# DoubleThumbs.net
KiCad netlist of a schematic drawn in EAGLE
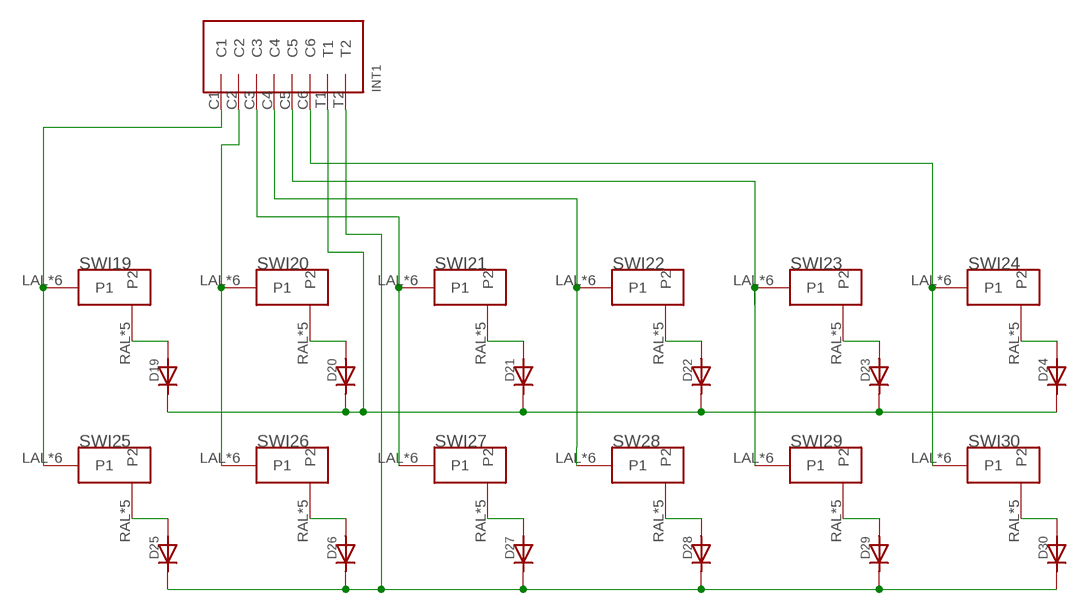
[diagram p0: schematic, sheet 1]

(export (version "E")
  (design (tool "Eeschema 10.0.6"))
  (components
    (comp (ref "D19")
      (value "DIODE")
      (footprint "eagle-import:DIODE_COMBO")
      (libsource (lib "eagle-import") (part "DIODE"))
    )
    (comp (ref "D20")
      (value "DIODE")
      (footprint "eagle-import:DIODE_COMBO")
      (libsource (lib "eagle-import") (part "DIODE"))
    )
    (comp (ref "D21")
      (value "DIODE")
      (footprint "eagle-import:DIODE_COMBO")
      (libsource (lib "eagle-import") (part "DIODE"))
    )
    (comp (ref "D22")
      (value "DIODE")
      (footprint "eagle-import:DIODE_COMBO")
      (libsource (lib "eagle-import") (part "DIODE"))
    )
    (comp (ref "D23")
      (value "DIODE")
      (footprint "eagle-import:DIODE_COMBO")
      (libsource (lib "eagle-import") (part "DIODE"))
    )
    (comp (ref "D24")
      (value "DIODE")
      (footprint "eagle-import:DIODE_COMBO")
      (libsource (lib "eagle-import") (part "DIODE"))
    )
    (comp (ref "D25")
      (value "DIODE")
      (footprint "eagle-import:DIODE_COMBO")
      (libsource (lib "eagle-import") (part "DIODE"))
    )
    (comp (ref "D26")
      (value "DIODE")
      (footprint "eagle-import:DIODE_COMBO")
      (libsource (lib "eagle-import") (part "DIODE"))
    )
    (comp (ref "D27")
      (value "DIODE")
      (footprint "eagle-import:DIODE_COMBO")
      (libsource (lib "eagle-import") (part "DIODE"))
    )
    (comp (ref "D28")
      (value "DIODE")
      (footprint "eagle-import:DIODE_COMBO")
      (libsource (lib "eagle-import") (part "DIODE"))
    )
    (comp (ref "D29")
      (value "DIODE")
      (footprint "eagle-import:DIODE_COMBO")
      (libsource (lib "eagle-import") (part "DIODE"))
    )
    (comp (ref "D30")
      (value "DIODE")
      (footprint "eagle-import:DIODE_COMBO")
      (libsource (lib "eagle-import") (part "DIODE"))
    )
    (comp (ref "INT1")
      (value "INTRCNNT4X2")
      (footprint "eagle-import:INTRRIBBON")
      (libsource (lib "eagle-import") (part "INTRCNNT4X2"))
    )
    (comp (ref "SW28")
      (value "MX/ALPSDOUBLESIDED")
      (footprint "eagle-import:DOUBLED_MX_ALPS")
      (libsource (lib "eagle-import") (part "MX/ALPSDOUBLESIDED"))
    )
    (comp (ref "SWI19")
      (value "MX/ALPSDOUBLESIDED")
      (footprint "eagle-import:DOUBLED_MX_ALPS")
      (libsource (lib "eagle-import") (part "MX/ALPSDOUBLESIDED"))
    )
    (comp (ref "SWI20")
      (value "MX/ALPSDOUBLESIDED")
      (footprint "eagle-import:DOUBLED_MX_ALPS")
      (libsource (lib "eagle-import") (part "MX/ALPSDOUBLESIDED"))
    )
    (comp (ref "SWI21")
      (value "MX/ALPSDOUBLESIDED")
      (footprint "eagle-import:DOUBLED_MX_ALPS")
      (libsource (lib "eagle-import") (part "MX/ALPSDOUBLESIDED"))
    )
    (comp (ref "SWI22")
      (value "MX/ALPSDOUBLESIDED")
      (footprint "eagle-import:DOUBLED_MX_ALPS")
      (libsource (lib "eagle-import") (part "MX/ALPSDOUBLESIDED"))
    )
    (comp (ref "SWI23")
      (value "MX/ALPSDOUBLESIDED")
      (footprint "eagle-import:DOUBLED_MX_ALPS")
      (libsource (lib "eagle-import") (part "MX/ALPSDOUBLESIDED"))
    )
    (comp (ref "SWI24")
      (value "MX/ALPSDOUBLESIDED")
      (footprint "eagle-import:DOUBLED_MX_ALPS")
      (libsource (lib "eagle-import") (part "MX/ALPSDOUBLESIDED"))
    )
    (comp (ref "SWI25")
      (value "MX/ALPSDOUBLESIDED")
      (footprint "eagle-import:DOUBLED_MX_ALPS")
      (libsource (lib "eagle-import") (part "MX/ALPSDOUBLESIDED"))
    )
    (comp (ref "SWI26")
      (value "MX/ALPSDOUBLESIDED")
      (footprint "eagle-import:DOUBLED_MX_ALPS")
      (libsource (lib "eagle-import") (part "MX/ALPSDOUBLESIDED"))
    )
    (comp (ref "SWI27")
      (value "MX/ALPSDOUBLESIDED")
      (footprint "eagle-import:DOUBLED_MX_ALPS")
      (libsource (lib "eagle-import") (part "MX/ALPSDOUBLESIDED"))
    )
    (comp (ref "SWI29")
      (value "MX/ALPSDOUBLESIDED")
      (footprint "eagle-import:DOUBLED_MX_ALPS")
      (libsource (lib "eagle-import") (part "MX/ALPSDOUBLESIDED"))
    )
    (comp (ref "SWI30")
      (value "MX/ALPSDOUBLESIDED")
      (footprint "eagle-import:DOUBLED_MX_ALPS")
      (libsource (lib "eagle-import") (part "MX/ALPSDOUBLESIDED"))
    )
  )
  (nets
    (net (code "1") (name "Net-(D19-AN-PadANOSB)") (class "Default")
      (node (ref "D19") (pin "ANOSB") (pinfunction "AN_ANOSB") (pintype "bidirectional"))
      (node (ref "D19") (pin "ANOST") (pinfunction "AN_ANOST") (pintype "bidirectional"))
      (node (ref "D19") (pin "ANOT") (pinfunction "AN_ANOT") (pintype "bidirectional"))
      (node (ref "SWI19") (pin "RAL") (pinfunction "P2_RAL") (pintype "bidirectional"))
      (node (ref "SWI19") (pin "RAR") (pinfunction "P2_RAR") (pintype "bidirectional"))
      (node (ref "SWI19") (pin "RCL") (pinfunction "P2_RCL") (pintype "bidirectional"))
      (node (ref "SWI19") (pin "RCR") (pinfunction "P2_RCR") (pintype "bidirectional"))
      (node (ref "SWI19") (pin "RLMID") (pinfunction "P2_RLMID") (pintype "bidirectional"))
    )
    (net (code "2") (name "Net-(D19-CAT-PadCATSB)") (class "Default")
      (node (ref "D19") (pin "CATSB") (pinfunction "CAT_CATSB") (pintype "bidirectional"))
      (node (ref "D19") (pin "CATST") (pinfunction "CAT_CATST") (pintype "bidirectional"))
      (node (ref "D19") (pin "CATT") (pinfunction "CAT_CATT") (pintype "bidirectional"))
      (node (ref "D20") (pin "CATSB") (pinfunction "CAT_CATSB") (pintype "bidirectional"))
      (node (ref "D20") (pin "CATST") (pinfunction "CAT_CATST") (pintype "bidirectional"))
      (node (ref "D20") (pin "CATT") (pinfunction "CAT_CATT") (pintype "bidirectional"))
      (node (ref "D21") (pin "CATSB") (pinfunction "CAT_CATSB") (pintype "bidirectional"))
      (node (ref "D21") (pin "CATST") (pinfunction "CAT_CATST") (pintype "bidirectional"))
      (node (ref "D21") (pin "CATT") (pinfunction "CAT_CATT") (pintype "bidirectional"))
      (node (ref "D22") (pin "CATSB") (pinfunction "CAT_CATSB") (pintype "bidirectional"))
      (node (ref "D22") (pin "CATST") (pinfunction "CAT_CATST") (pintype "bidirectional"))
      (node (ref "D22") (pin "CATT") (pinfunction "CAT_CATT") (pintype "bidirectional"))
      (node (ref "D23") (pin "CATSB") (pinfunction "CAT_CATSB") (pintype "bidirectional"))
      (node (ref "D23") (pin "CATST") (pinfunction "CAT_CATST") (pintype "bidirectional"))
      (node (ref "D23") (pin "CATT") (pinfunction "CAT_CATT") (pintype "bidirectional"))
      (node (ref "D24") (pin "CATSB") (pinfunction "CAT_CATSB") (pintype "bidirectional"))
      (node (ref "D24") (pin "CATST") (pinfunction "CAT_CATST") (pintype "bidirectional"))
      (node (ref "D24") (pin "CATT") (pinfunction "CAT_CATT") (pintype "bidirectional"))
      (node (ref "INT1") (pin "T1") (pinfunction "T1_T1") (pintype "bidirectional"))
    )
    (net (code "3") (name "Net-(D20-AN-PadANOSB)") (class "Default")
      (node (ref "D20") (pin "ANOSB") (pinfunction "AN_ANOSB") (pintype "bidirectional"))
      (node (ref "D20") (pin "ANOST") (pinfunction "AN_ANOST") (pintype "bidirectional"))
      (node (ref "D20") (pin "ANOT") (pinfunction "AN_ANOT") (pintype "bidirectional"))
      (node (ref "SWI20") (pin "RAL") (pinfunction "P2_RAL") (pintype "bidirectional"))
      (node (ref "SWI20") (pin "RAR") (pinfunction "P2_RAR") (pintype "bidirectional"))
      (node (ref "SWI20") (pin "RCL") (pinfunction "P2_RCL") (pintype "bidirectional"))
      (node (ref "SWI20") (pin "RCR") (pinfunction "P2_RCR") (pintype "bidirectional"))
      (node (ref "SWI20") (pin "RLMID") (pinfunction "P2_RLMID") (pintype "bidirectional"))
    )
    (net (code "4") (name "Net-(D21-AN-PadANOSB)") (class "Default")
      (node (ref "D21") (pin "ANOSB") (pinfunction "AN_ANOSB") (pintype "bidirectional"))
      (node (ref "D21") (pin "ANOST") (pinfunction "AN_ANOST") (pintype "bidirectional"))
      (node (ref "D21") (pin "ANOT") (pinfunction "AN_ANOT") (pintype "bidirectional"))
      (node (ref "SWI21") (pin "RAL") (pinfunction "P2_RAL") (pintype "bidirectional"))
      (node (ref "SWI21") (pin "RAR") (pinfunction "P2_RAR") (pintype "bidirectional"))
      (node (ref "SWI21") (pin "RCL") (pinfunction "P2_RCL") (pintype "bidirectional"))
      (node (ref "SWI21") (pin "RCR") (pinfunction "P2_RCR") (pintype "bidirectional"))
      (node (ref "SWI21") (pin "RLMID") (pinfunction "P2_RLMID") (pintype "bidirectional"))
    )
    (net (code "5") (name "Net-(D22-AN-PadANOSB)") (class "Default")
      (node (ref "D22") (pin "ANOSB") (pinfunction "AN_ANOSB") (pintype "bidirectional"))
      (node (ref "D22") (pin "ANOST") (pinfunction "AN_ANOST") (pintype "bidirectional"))
      (node (ref "D22") (pin "ANOT") (pinfunction "AN_ANOT") (pintype "bidirectional"))
      (node (ref "SWI22") (pin "RAL") (pinfunction "P2_RAL") (pintype "bidirectional"))
      (node (ref "SWI22") (pin "RAR") (pinfunction "P2_RAR") (pintype "bidirectional"))
      (node (ref "SWI22") (pin "RCL") (pinfunction "P2_RCL") (pintype "bidirectional"))
      (node (ref "SWI22") (pin "RCR") (pinfunction "P2_RCR") (pintype "bidirectional"))
      (node (ref "SWI22") (pin "RLMID") (pinfunction "P2_RLMID") (pintype "bidirectional"))
    )
    (net (code "6") (name "Net-(D23-AN-PadANOSB)") (class "Default")
      (node (ref "D23") (pin "ANOSB") (pinfunction "AN_ANOSB") (pintype "bidirectional"))
      (node (ref "D23") (pin "ANOST") (pinfunction "AN_ANOST") (pintype "bidirectional"))
      (node (ref "D23") (pin "ANOT") (pinfunction "AN_ANOT") (pintype "bidirectional"))
      (node (ref "SWI23") (pin "RAL") (pinfunction "P2_RAL") (pintype "bidirectional"))
      (node (ref "SWI23") (pin "RAR") (pinfunction "P2_RAR") (pintype "bidirectional"))
      (node (ref "SWI23") (pin "RCL") (pinfunction "P2_RCL") (pintype "bidirectional"))
      (node (ref "SWI23") (pin "RCR") (pinfunction "P2_RCR") (pintype "bidirectional"))
      (node (ref "SWI23") (pin "RLMID") (pinfunction "P2_RLMID") (pintype "bidirectional"))
    )
    (net (code "7") (name "Net-(D24-AN-PadANOSB)") (class "Default")
      (node (ref "D24") (pin "ANOSB") (pinfunction "AN_ANOSB") (pintype "bidirectional"))
      (node (ref "D24") (pin "ANOST") (pinfunction "AN_ANOST") (pintype "bidirectional"))
      (node (ref "D24") (pin "ANOT") (pinfunction "AN_ANOT") (pintype "bidirectional"))
      (node (ref "SWI24") (pin "RAL") (pinfunction "P2_RAL") (pintype "bidirectional"))
      (node (ref "SWI24") (pin "RAR") (pinfunction "P2_RAR") (pintype "bidirectional"))
      (node (ref "SWI24") (pin "RCL") (pinfunction "P2_RCL") (pintype "bidirectional"))
      (node (ref "SWI24") (pin "RCR") (pinfunction "P2_RCR") (pintype "bidirectional"))
      (node (ref "SWI24") (pin "RLMID") (pinfunction "P2_RLMID") (pintype "bidirectional"))
    )
    (net (code "8") (name "Net-(D25-AN-PadANOSB)") (class "Default")
      (node (ref "D25") (pin "ANOSB") (pinfunction "AN_ANOSB") (pintype "bidirectional"))
      (node (ref "D25") (pin "ANOST") (pinfunction "AN_ANOST") (pintype "bidirectional"))
      (node (ref "D25") (pin "ANOT") (pinfunction "AN_ANOT") (pintype "bidirectional"))
      (node (ref "SWI25") (pin "RAL") (pinfunction "P2_RAL") (pintype "bidirectional"))
      (node (ref "SWI25") (pin "RAR") (pinfunction "P2_RAR") (pintype "bidirectional"))
      (node (ref "SWI25") (pin "RCL") (pinfunction "P2_RCL") (pintype "bidirectional"))
      (node (ref "SWI25") (pin "RCR") (pinfunction "P2_RCR") (pintype "bidirectional"))
      (node (ref "SWI25") (pin "RLMID") (pinfunction "P2_RLMID") (pintype "bidirectional"))
    )
    (net (code "9") (name "Net-(D25-CAT-PadCATSB)") (class "Default")
      (node (ref "D25") (pin "CATSB") (pinfunction "CAT_CATSB") (pintype "bidirectional"))
      (node (ref "D25") (pin "CATST") (pinfunction "CAT_CATST") (pintype "bidirectional"))
      (node (ref "D25") (pin "CATT") (pinfunction "CAT_CATT") (pintype "bidirectional"))
      (node (ref "D26") (pin "CATSB") (pinfunction "CAT_CATSB") (pintype "bidirectional"))
      (node (ref "D26") (pin "CATST") (pinfunction "CAT_CATST") (pintype "bidirectional"))
      (node (ref "D26") (pin "CATT") (pinfunction "CAT_CATT") (pintype "bidirectional"))
      (node (ref "D27") (pin "CATSB") (pinfunction "CAT_CATSB") (pintype "bidirectional"))
      (node (ref "D27") (pin "CATST") (pinfunction "CAT_CATST") (pintype "bidirectional"))
      (node (ref "D27") (pin "CATT") (pinfunction "CAT_CATT") (pintype "bidirectional"))
      (node (ref "D28") (pin "CATSB") (pinfunction "CAT_CATSB") (pintype "bidirectional"))
      (node (ref "D28") (pin "CATST") (pinfunction "CAT_CATST") (pintype "bidirectional"))
      (node (ref "D28") (pin "CATT") (pinfunction "CAT_CATT") (pintype "bidirectional"))
      (node (ref "D29") (pin "CATSB") (pinfunction "CAT_CATSB") (pintype "bidirectional"))
      (node (ref "D29") (pin "CATST") (pinfunction "CAT_CATST") (pintype "bidirectional"))
      (node (ref "D29") (pin "CATT") (pinfunction "CAT_CATT") (pintype "bidirectional"))
      (node (ref "D30") (pin "CATSB") (pinfunction "CAT_CATSB") (pintype "bidirectional"))
      (node (ref "D30") (pin "CATST") (pinfunction "CAT_CATST") (pintype "bidirectional"))
      (node (ref "D30") (pin "CATT") (pinfunction "CAT_CATT") (pintype "bidirectional"))
      (node (ref "INT1") (pin "T2") (pinfunction "T2_T2") (pintype "bidirectional"))
    )
    (net (code "10") (name "Net-(D26-AN-PadANOSB)") (class "Default")
      (node (ref "D26") (pin "ANOSB") (pinfunction "AN_ANOSB") (pintype "bidirectional"))
      (node (ref "D26") (pin "ANOST") (pinfunction "AN_ANOST") (pintype "bidirectional"))
      (node (ref "D26") (pin "ANOT") (pinfunction "AN_ANOT") (pintype "bidirectional"))
      (node (ref "SWI26") (pin "RAL") (pinfunction "P2_RAL") (pintype "bidirectional"))
      (node (ref "SWI26") (pin "RAR") (pinfunction "P2_RAR") (pintype "bidirectional"))
      (node (ref "SWI26") (pin "RCL") (pinfunction "P2_RCL") (pintype "bidirectional"))
      (node (ref "SWI26") (pin "RCR") (pinfunction "P2_RCR") (pintype "bidirectional"))
      (node (ref "SWI26") (pin "RLMID") (pinfunction "P2_RLMID") (pintype "bidirectional"))
    )
    (net (code "11") (name "Net-(D27-AN-PadANOSB)") (class "Default")
      (node (ref "D27") (pin "ANOSB") (pinfunction "AN_ANOSB") (pintype "bidirectional"))
      (node (ref "D27") (pin "ANOST") (pinfunction "AN_ANOST") (pintype "bidirectional"))
      (node (ref "D27") (pin "ANOT") (pinfunction "AN_ANOT") (pintype "bidirectional"))
      (node (ref "SWI27") (pin "RAL") (pinfunction "P2_RAL") (pintype "bidirectional"))
      (node (ref "SWI27") (pin "RAR") (pinfunction "P2_RAR") (pintype "bidirectional"))
      (node (ref "SWI27") (pin "RCL") (pinfunction "P2_RCL") (pintype "bidirectional"))
      (node (ref "SWI27") (pin "RCR") (pinfunction "P2_RCR") (pintype "bidirectional"))
      (node (ref "SWI27") (pin "RLMID") (pinfunction "P2_RLMID") (pintype "bidirectional"))
    )
    (net (code "12") (name "Net-(D28-AN-PadANOSB)") (class "Default")
      (node (ref "D28") (pin "ANOSB") (pinfunction "AN_ANOSB") (pintype "bidirectional"))
      (node (ref "D28") (pin "ANOST") (pinfunction "AN_ANOST") (pintype "bidirectional"))
      (node (ref "D28") (pin "ANOT") (pinfunction "AN_ANOT") (pintype "bidirectional"))
      (node (ref "SW28") (pin "RAL") (pinfunction "P2_RAL") (pintype "bidirectional"))
      (node (ref "SW28") (pin "RAR") (pinfunction "P2_RAR") (pintype "bidirectional"))
      (node (ref "SW28") (pin "RCL") (pinfunction "P2_RCL") (pintype "bidirectional"))
      (node (ref "SW28") (pin "RCR") (pinfunction "P2_RCR") (pintype "bidirectional"))
      (node (ref "SW28") (pin "RLMID") (pinfunction "P2_RLMID") (pintype "bidirectional"))
    )
    (net (code "13") (name "Net-(D29-AN-PadANOSB)") (class "Default")
      (node (ref "D29") (pin "ANOSB") (pinfunction "AN_ANOSB") (pintype "bidirectional"))
      (node (ref "D29") (pin "ANOST") (pinfunction "AN_ANOST") (pintype "bidirectional"))
      (node (ref "D29") (pin "ANOT") (pinfunction "AN_ANOT") (pintype "bidirectional"))
      (node (ref "SWI29") (pin "RAL") (pinfunction "P2_RAL") (pintype "bidirectional"))
      (node (ref "SWI29") (pin "RAR") (pinfunction "P2_RAR") (pintype "bidirectional"))
      (node (ref "SWI29") (pin "RCL") (pinfunction "P2_RCL") (pintype "bidirectional"))
      (node (ref "SWI29") (pin "RCR") (pinfunction "P2_RCR") (pintype "bidirectional"))
      (node (ref "SWI29") (pin "RLMID") (pinfunction "P2_RLMID") (pintype "bidirectional"))
    )
    (net (code "14") (name "Net-(D30-AN-PadANOSB)") (class "Default")
      (node (ref "D30") (pin "ANOSB") (pinfunction "AN_ANOSB") (pintype "bidirectional"))
      (node (ref "D30") (pin "ANOST") (pinfunction "AN_ANOST") (pintype "bidirectional"))
      (node (ref "D30") (pin "ANOT") (pinfunction "AN_ANOT") (pintype "bidirectional"))
      (node (ref "SWI30") (pin "RAL") (pinfunction "P2_RAL") (pintype "bidirectional"))
      (node (ref "SWI30") (pin "RAR") (pinfunction "P2_RAR") (pintype "bidirectional"))
      (node (ref "SWI30") (pin "RCL") (pinfunction "P2_RCL") (pintype "bidirectional"))
      (node (ref "SWI30") (pin "RCR") (pinfunction "P2_RCR") (pintype "bidirectional"))
      (node (ref "SWI30") (pin "RLMID") (pinfunction "P2_RLMID") (pintype "bidirectional"))
    )
    (net (code "15") (name "Net-(INT1-PadC1)") (class "Default")
      (node (ref "INT1") (pin "C1") (pinfunction "C1_C1") (pintype "bidirectional"))
      (node (ref "SWI19") (pin "LAL") (pinfunction "P1_LAL") (pintype "bidirectional"))
      (node (ref "SWI19") (pin "LAR") (pinfunction "P1_LAR") (pintype "bidirectional"))
      (node (ref "SWI19") (pin "LCL") (pinfunction "P1_LCL") (pintype "bidirectional"))
      (node (ref "SWI19") (pin "LCR") (pinfunction "P1_LCR") (pintype "bidirectional"))
      (node (ref "SWI19") (pin "LLP") (pinfunction "P1_LLP") (pintype "bidirectional"))
      (node (ref "SWI19") (pin "LRLP") (pinfunction "P1_LRLP") (pintype "bidirectional"))
      (node (ref "SWI25") (pin "LAL") (pinfunction "P1_LAL") (pintype "bidirectional"))
      (node (ref "SWI25") (pin "LAR") (pinfunction "P1_LAR") (pintype "bidirectional"))
      (node (ref "SWI25") (pin "LCL") (pinfunction "P1_LCL") (pintype "bidirectional"))
      (node (ref "SWI25") (pin "LCR") (pinfunction "P1_LCR") (pintype "bidirectional"))
      (node (ref "SWI25") (pin "LLP") (pinfunction "P1_LLP") (pintype "bidirectional"))
      (node (ref "SWI25") (pin "LRLP") (pinfunction "P1_LRLP") (pintype "bidirectional"))
    )
    (net (code "16") (name "Net-(INT1-PadC2)") (class "Default")
      (node (ref "INT1") (pin "C2") (pinfunction "C2_C2") (pintype "bidirectional"))
      (node (ref "SWI20") (pin "LAL") (pinfunction "P1_LAL") (pintype "bidirectional"))
      (node (ref "SWI20") (pin "LAR") (pinfunction "P1_LAR") (pintype "bidirectional"))
      (node (ref "SWI20") (pin "LCL") (pinfunction "P1_LCL") (pintype "bidirectional"))
      (node (ref "SWI20") (pin "LCR") (pinfunction "P1_LCR") (pintype "bidirectional"))
      (node (ref "SWI20") (pin "LLP") (pinfunction "P1_LLP") (pintype "bidirectional"))
      (node (ref "SWI20") (pin "LRLP") (pinfunction "P1_LRLP") (pintype "bidirectional"))
      (node (ref "SWI26") (pin "LAL") (pinfunction "P1_LAL") (pintype "bidirectional"))
      (node (ref "SWI26") (pin "LAR") (pinfunction "P1_LAR") (pintype "bidirectional"))
      (node (ref "SWI26") (pin "LCL") (pinfunction "P1_LCL") (pintype "bidirectional"))
      (node (ref "SWI26") (pin "LCR") (pinfunction "P1_LCR") (pintype "bidirectional"))
      (node (ref "SWI26") (pin "LLP") (pinfunction "P1_LLP") (pintype "bidirectional"))
      (node (ref "SWI26") (pin "LRLP") (pinfunction "P1_LRLP") (pintype "bidirectional"))
    )
    (net (code "17") (name "Net-(INT1-PadC3)") (class "Default")
      (node (ref "INT1") (pin "C3") (pinfunction "C3_C3") (pintype "bidirectional"))
      (node (ref "SWI21") (pin "LAL") (pinfunction "P1_LAL") (pintype "bidirectional"))
      (node (ref "SWI21") (pin "LAR") (pinfunction "P1_LAR") (pintype "bidirectional"))
      (node (ref "SWI21") (pin "LCL") (pinfunction "P1_LCL") (pintype "bidirectional"))
      (node (ref "SWI21") (pin "LCR") (pinfunction "P1_LCR") (pintype "bidirectional"))
      (node (ref "SWI21") (pin "LLP") (pinfunction "P1_LLP") (pintype "bidirectional"))
      (node (ref "SWI21") (pin "LRLP") (pinfunction "P1_LRLP") (pintype "bidirectional"))
      (node (ref "SWI27") (pin "LAL") (pinfunction "P1_LAL") (pintype "bidirectional"))
      (node (ref "SWI27") (pin "LAR") (pinfunction "P1_LAR") (pintype "bidirectional"))
      (node (ref "SWI27") (pin "LCL") (pinfunction "P1_LCL") (pintype "bidirectional"))
      (node (ref "SWI27") (pin "LCR") (pinfunction "P1_LCR") (pintype "bidirectional"))
      (node (ref "SWI27") (pin "LLP") (pinfunction "P1_LLP") (pintype "bidirectional"))
      (node (ref "SWI27") (pin "LRLP") (pinfunction "P1_LRLP") (pintype "bidirectional"))
    )
    (net (code "18") (name "Net-(INT1-PadC4)") (class "Default")
      (node (ref "INT1") (pin "C4") (pinfunction "C4_C4") (pintype "bidirectional"))
      (node (ref "SW28") (pin "LAL") (pinfunction "P1_LAL") (pintype "bidirectional"))
      (node (ref "SW28") (pin "LAR") (pinfunction "P1_LAR") (pintype "bidirectional"))
      (node (ref "SW28") (pin "LCL") (pinfunction "P1_LCL") (pintype "bidirectional"))
      (node (ref "SW28") (pin "LCR") (pinfunction "P1_LCR") (pintype "bidirectional"))
      (node (ref "SW28") (pin "LLP") (pinfunction "P1_LLP") (pintype "bidirectional"))
      (node (ref "SW28") (pin "LRLP") (pinfunction "P1_LRLP") (pintype "bidirectional"))
      (node (ref "SWI22") (pin "LAL") (pinfunction "P1_LAL") (pintype "bidirectional"))
      (node (ref "SWI22") (pin "LAR") (pinfunction "P1_LAR") (pintype "bidirectional"))
      (node (ref "SWI22") (pin "LCL") (pinfunction "P1_LCL") (pintype "bidirectional"))
      (node (ref "SWI22") (pin "LCR") (pinfunction "P1_LCR") (pintype "bidirectional"))
      (node (ref "SWI22") (pin "LLP") (pinfunction "P1_LLP") (pintype "bidirectional"))
      (node (ref "SWI22") (pin "LRLP") (pinfunction "P1_LRLP") (pintype "bidirectional"))
    )
    (net (code "19") (name "Net-(INT1-PadC5)") (class "Default")
      (node (ref "INT1") (pin "C5") (pinfunction "C5_C5") (pintype "bidirectional"))
      (node (ref "SWI23") (pin "LAL") (pinfunction "P1_LAL") (pintype "bidirectional"))
      (node (ref "SWI23") (pin "LAR") (pinfunction "P1_LAR") (pintype "bidirectional"))
      (node (ref "SWI23") (pin "LCL") (pinfunction "P1_LCL") (pintype "bidirectional"))
      (node (ref "SWI23") (pin "LCR") (pinfunction "P1_LCR") (pintype "bidirectional"))
      (node (ref "SWI23") (pin "LLP") (pinfunction "P1_LLP") (pintype "bidirectional"))
      (node (ref "SWI23") (pin "LRLP") (pinfunction "P1_LRLP") (pintype "bidirectional"))
      (node (ref "SWI29") (pin "LAL") (pinfunction "P1_LAL") (pintype "bidirectional"))
      (node (ref "SWI29") (pin "LAR") (pinfunction "P1_LAR") (pintype "bidirectional"))
      (node (ref "SWI29") (pin "LCL") (pinfunction "P1_LCL") (pintype "bidirectional"))
      (node (ref "SWI29") (pin "LCR") (pinfunction "P1_LCR") (pintype "bidirectional"))
      (node (ref "SWI29") (pin "LLP") (pinfunction "P1_LLP") (pintype "bidirectional"))
      (node (ref "SWI29") (pin "LRLP") (pinfunction "P1_LRLP") (pintype "bidirectional"))
    )
    (net (code "20") (name "Net-(INT1-PadC6)") (class "Default")
      (node (ref "INT1") (pin "C6") (pinfunction "C6_C6") (pintype "bidirectional"))
      (node (ref "SWI24") (pin "LAL") (pinfunction "P1_LAL") (pintype "bidirectional"))
      (node (ref "SWI24") (pin "LAR") (pinfunction "P1_LAR") (pintype "bidirectional"))
      (node (ref "SWI24") (pin "LCL") (pinfunction "P1_LCL") (pintype "bidirectional"))
      (node (ref "SWI24") (pin "LCR") (pinfunction "P1_LCR") (pintype "bidirectional"))
      (node (ref "SWI24") (pin "LLP") (pinfunction "P1_LLP") (pintype "bidirectional"))
      (node (ref "SWI24") (pin "LRLP") (pinfunction "P1_LRLP") (pintype "bidirectional"))
      (node (ref "SWI30") (pin "LAL") (pinfunction "P1_LAL") (pintype "bidirectional"))
      (node (ref "SWI30") (pin "LAR") (pinfunction "P1_LAR") (pintype "bidirectional"))
      (node (ref "SWI30") (pin "LCL") (pinfunction "P1_LCL") (pintype "bidirectional"))
      (node (ref "SWI30") (pin "LCR") (pinfunction "P1_LCR") (pintype "bidirectional"))
      (node (ref "SWI30") (pin "LLP") (pinfunction "P1_LLP") (pintype "bidirectional"))
      (node (ref "SWI30") (pin "LRLP") (pinfunction "P1_LRLP") (pintype "bidirectional"))
    )
  )
)
